# LTC.net
KiCad netlist of a schematic drawn in Altium Designer
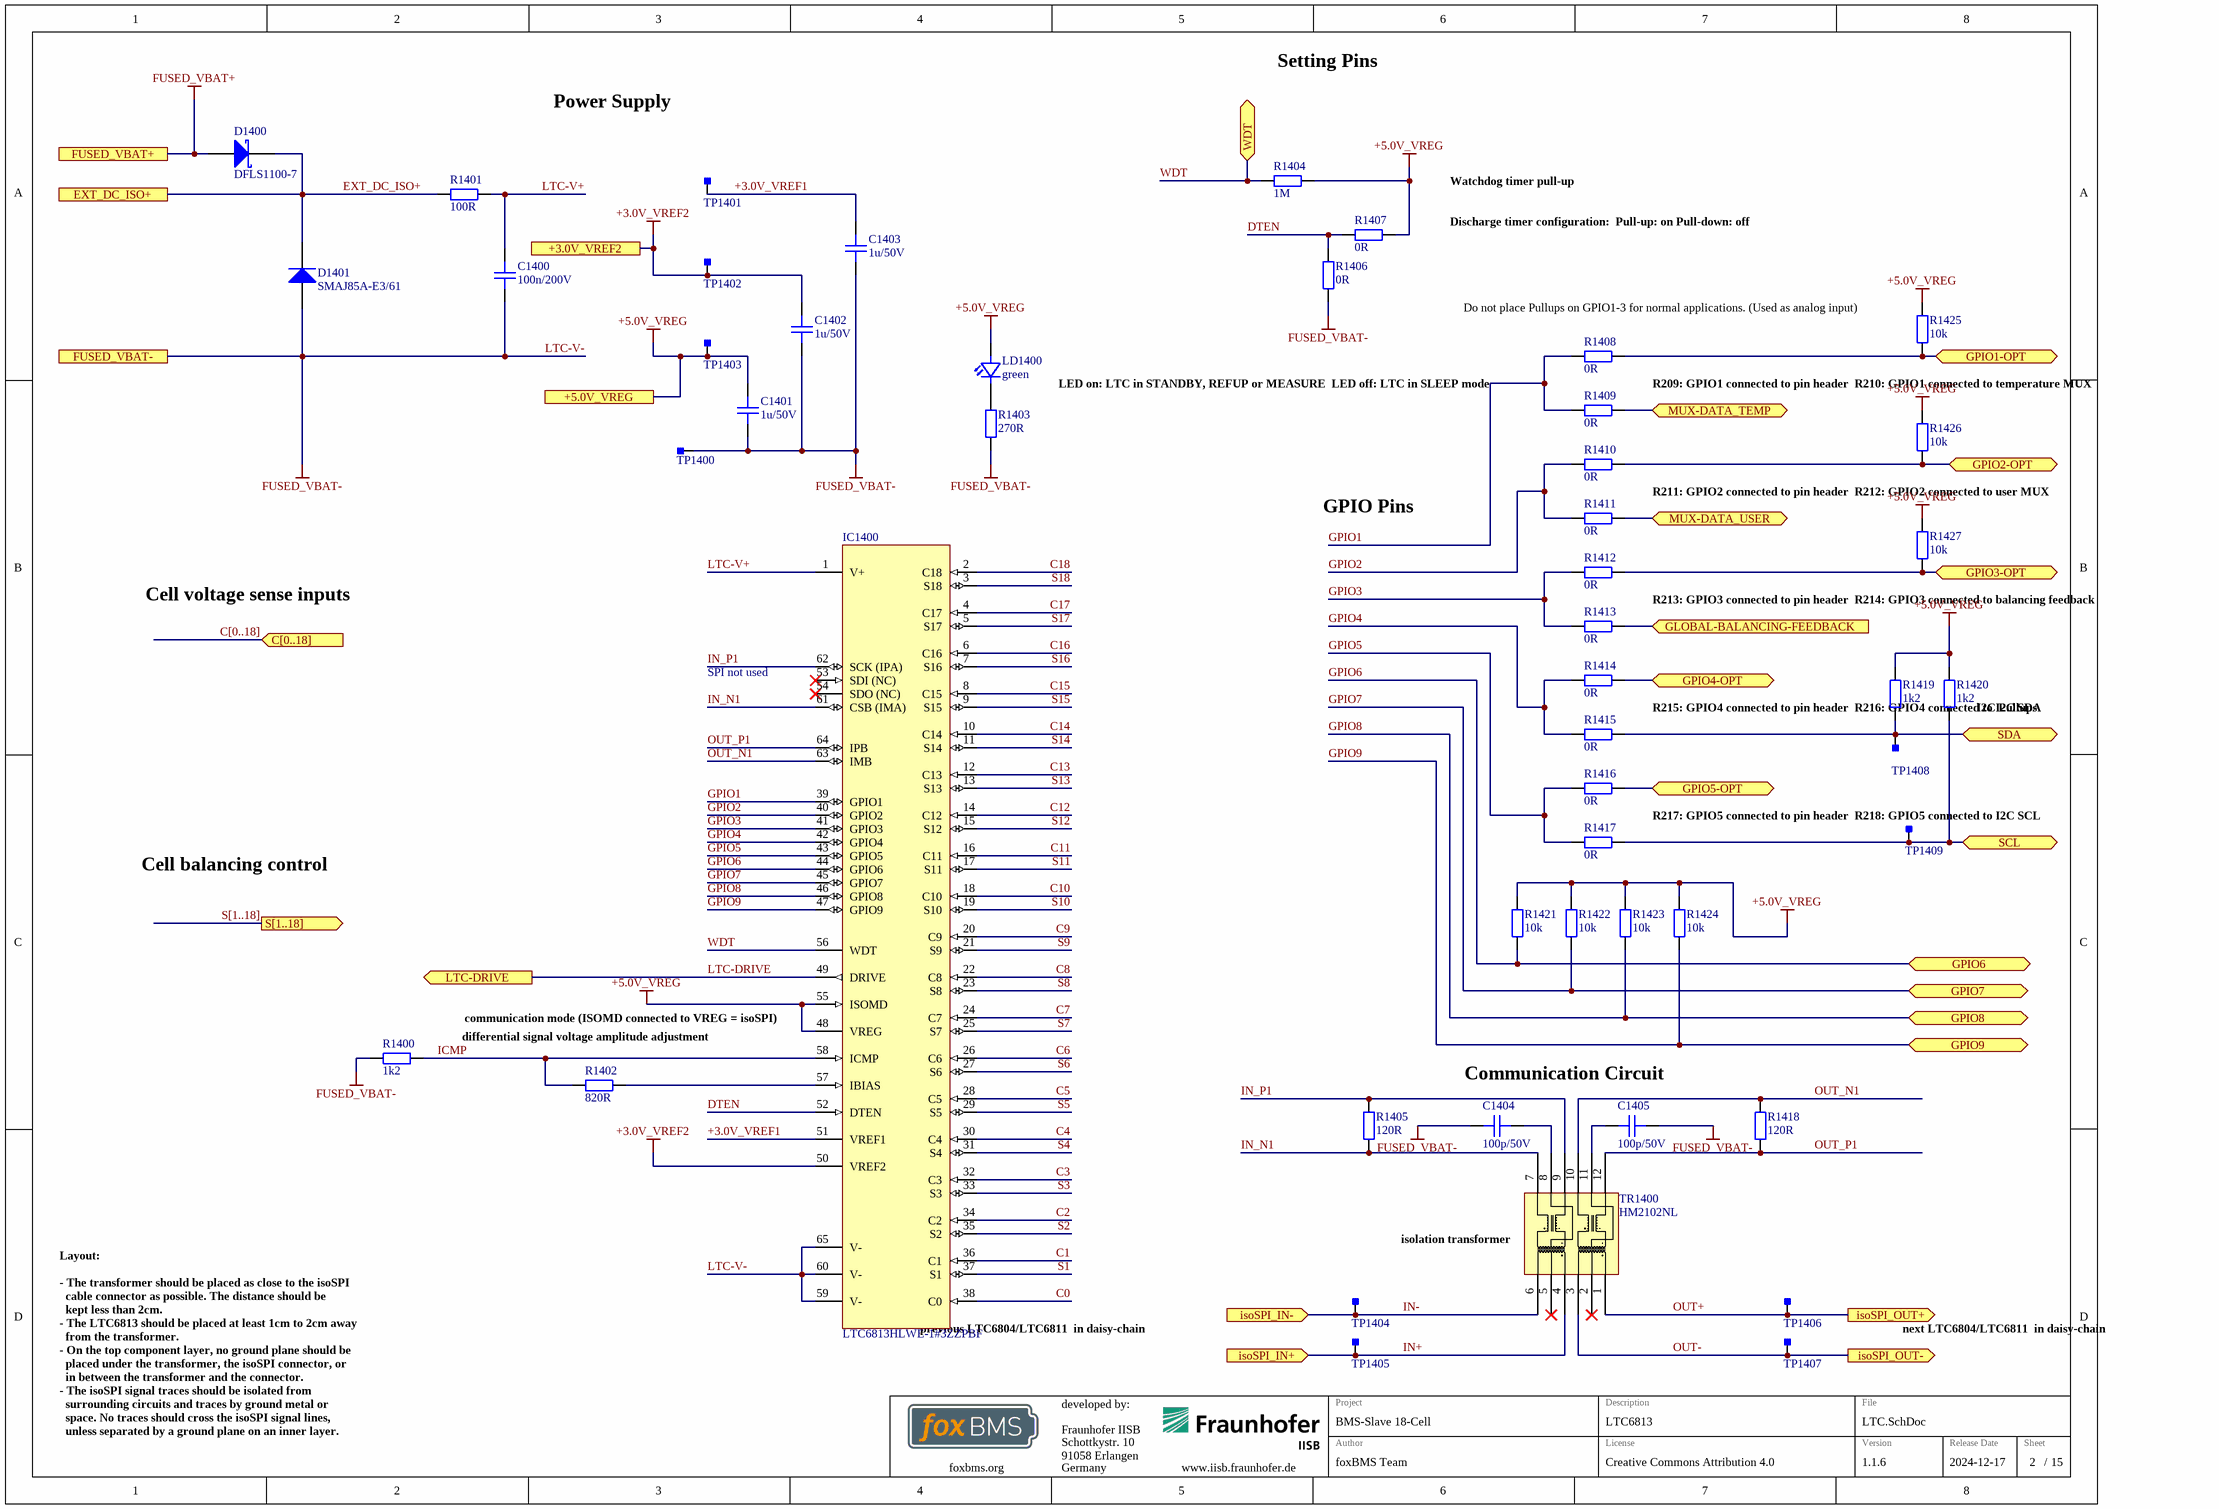
[diagram p0: LTC.SchDoc]

(export (version "E")
  (design (tool "Eeschema 10.0.6"))
  (components
    (comp (ref "C1400")
      (value "100n/200V")
      (footprint "CAPC3216X18N")
      (description "MLCC")
      (fields (field (name "PART NUMBER") "gen_C_ceramic_100n_200V_X7R_1206"))
      (libsource (lib "OE750") (part "C"))
    )
    (comp (ref "C1401")
      (value "1u/50V")
      (footprint "CAPC2012X14N")
      (description "MLCC")
      (fields (field (name "PART NUMBER") "gen_C_ceramic_1u_50V_X7R_0805") (field (name "TOLERANCE") "± 10%"))
      (libsource (lib "OE750") (part "C"))
    )
    (comp (ref "C1402")
      (value "1u/50V")
      (footprint "CAPC2012X14N")
      (description "MLCC")
      (fields (field (name "PART NUMBER") "gen_C_ceramic_1u_50V_X7R_0805") (field (name "TOLERANCE") "± 10%"))
      (libsource (lib "OE750") (part "C"))
    )
    (comp (ref "C1403")
      (value "1u/50V")
      (footprint "CAPC2012X14N")
      (description "MLCC")
      (fields (field (name "PART NUMBER") "gen_C_ceramic_1u_50V_X7R_0805") (field (name "TOLERANCE") "± 10%"))
      (libsource (lib "OE750") (part "C"))
    )
    (comp (ref "C1404")
      (value "100p/50V")
      (footprint "CAPC1608X08N")
      (description "MLCC")
      (fields
        (field (name "PART NUMBER") "gen_C_ceramic_100p_50V_C0G_0603")
        (field (name "TOLERANCE") "± 10%")
      )
      (libsource (lib "OE750") (part "C"))
    )
    (comp (ref "C1405")
      (value "100p/50V")
      (footprint "CAPC1608X08N")
      (description "MLCC")
      (fields
        (field (name "PART NUMBER") "gen_C_ceramic_100p_50V_C0G_0603")
        (field (name "TOLERANCE") "± 10%")
      )
      (libsource (lib "OE750") (part "C"))
    )
    (comp (ref "D1400")
      (value "DFLS1100-7")
      (footprint "DIOD-POWERDI123-2_V")
      (fields (field (name "MANUFACTURER") "Diodes Inc"))
      (libsource (lib "Altium Content Vault") (part "DSKY-AK-2"))
    )
    (comp (ref "D1401")
      (value "SMAJ85A-E3/61")
      (footprint "VISH-DO-214AC-2_L")
      (fields (field (name "MANUFACTURER") "Vishay Semiconductor"))
      (libsource (lib "Altium Content Vault") (part "VISH-K1A2-2"))
    )
    (comp (ref "IC1400")
      (value "LTC6813HLWE-1#3ZZPBF")
      (footprint "TSQFP50P1200X1200X160_HS-65N")
      (description "18 Cell Multicell Battery Monitor, -40 to 125 degC, Pb-Free")
      (fields (field (name "PARTNUMBER") "LTC6811HG-1#PBF") (field (name "MANUFACTURER") "Linear Technology"))
      (libsource (lib "OE750") (part "LTC6813HLWE-1#3ZZPBF"))
    )
    (comp (ref "LD1400")
      (value "green")
      (footprint "LEDC1608X07N")
      (description "TLMG1100-GS08")
      (fields (field (name "PART NUMBER") "LED_0603_green_AECQ") (field (name "MANUFACTURER") "Vishay"))
      (libsource (lib "OE750") (part "D_LED"))
    )
    (comp (ref "R1400")
      (value "1k2")
      (footprint "RESC1608X05N")
      (description "SMD Resistor 1k2 0603")
      (fields (field (name "PART NUMBER") "gen_R_1k2_0603") (field (name "TOLERANCE") "1%"))
      (libsource (lib "OE750") (part "R"))
    )
    (comp (ref "R1401")
      (value "100R")
      (footprint "RESC2012X05N")
      (description "SMD Resistor 100R 0805")
      (fields (field (name "PART NUMBER") "gen_R_100R_0805") (field (name "TOLERANCE") "1%"))
      (libsource (lib "OE750") (part "R"))
    )
    (comp (ref "R1402")
      (value "820R")
      (footprint "RESC1608X05N")
      (description "SMD Resistor 820R 0603")
      (fields (field (name "PART NUMBER") "gen_R_820R_0603") (field (name "TOLERANCE") "1%"))
      (libsource (lib "OE750") (part "R"))
    )
    (comp (ref "R1403")
      (value "270R")
      (footprint "RESC1608X05N")
      (description "SMD Resistor 270R 0603")
      (fields (field (name "PART NUMBER") "gen_R_270R_0603") (field (name "TOLERANCE") "1%"))
      (libsource (lib "OE750") (part "R"))
    )
    (comp (ref "R1404")
      (value "1M")
      (footprint "RESC1608X05N")
      (description "SMD Resistor 1M 0603")
      (fields (field (name "PART NUMBER") "gen_R_1M_0603") (field (name "TOLERANCE") "1%"))
      (libsource (lib "OE750") (part "R"))
    )
    (comp (ref "R1405")
      (value "120R")
      (footprint "RESC1608X05N")
      (description "SMD Resistor 120R 0603")
      (fields (field (name "PART NUMBER") "gen_R_120R_0603") (field (name "TOLERANCE") "1%"))
      (libsource (lib "OE750") (part "R"))
    )
    (comp (ref "R1406")
      (value "0R")
      (footprint "RESC1608X05N")
      (description "SMD Resistor 0R 0603")
      (fields (field (name "PART NUMBER") "gen_R_0R_0603") (field (name "POWER") "0.1W"))
      (libsource (lib "OE750") (part "R"))
    )
    (comp (ref "R1407")
      (value "0R")
      (footprint "RESC1608X05N")
      (description "SMD Resistor 0R 0603")
      (fields (field (name "PART NUMBER") "gen_R_0R_0603") (field (name "POWER") "0.1W"))
      (libsource (lib "OE750") (part "R"))
    )
    (comp (ref "R1408")
      (value "0R")
      (footprint "RESC1608X05N")
      (description "SMD Resistor 0R 0603")
      (fields (field (name "PART NUMBER") "gen_R_0R_0603") (field (name "POWER") "0.1W"))
      (libsource (lib "OE750") (part "R"))
    )
    (comp (ref "R1409")
      (value "0R")
      (footprint "RESC1608X05N")
      (description "SMD Resistor 0R 0603")
      (fields (field (name "PART NUMBER") "gen_R_0R_0603") (field (name "POWER") "0.1W"))
      (libsource (lib "OE750") (part "R"))
    )
    (comp (ref "R1410")
      (value "0R")
      (footprint "RESC1608X05N")
      (description "SMD Resistor 0R 0603")
      (fields (field (name "PART NUMBER") "gen_R_0R_0603") (field (name "POWER") "0.1W"))
      (libsource (lib "OE750") (part "R"))
    )
    (comp (ref "R1411")
      (value "0R")
      (footprint "RESC1608X05N")
      (description "SMD Resistor 0R 0603")
      (fields (field (name "PART NUMBER") "gen_R_0R_0603") (field (name "POWER") "0.1W"))
      (libsource (lib "OE750") (part "R"))
    )
    (comp (ref "R1412")
      (value "0R")
      (footprint "RESC1608X05N")
      (description "SMD Resistor 0R 0603")
      (fields (field (name "PART NUMBER") "gen_R_0R_0603") (field (name "POWER") "0.1W"))
      (libsource (lib "OE750") (part "R"))
    )
    (comp (ref "R1413")
      (value "0R")
      (footprint "RESC1608X05N")
      (description "SMD Resistor 0R 0603")
      (fields (field (name "PART NUMBER") "gen_R_0R_0603") (field (name "POWER") "0.1W"))
      (libsource (lib "OE750") (part "R"))
    )
    (comp (ref "R1414")
      (value "0R")
      (footprint "RESC1608X05N")
      (description "SMD Resistor 0R 0603")
      (fields (field (name "PART NUMBER") "gen_R_0R_0603") (field (name "POWER") "0.1W"))
      (libsource (lib "OE750") (part "R"))
    )
    (comp (ref "R1415")
      (value "0R")
      (footprint "RESC1608X05N")
      (description "SMD Resistor 0R 0603")
      (fields (field (name "PART NUMBER") "gen_R_0R_0603") (field (name "POWER") "0.1W"))
      (libsource (lib "OE750") (part "R"))
    )
    (comp (ref "R1416")
      (value "0R")
      (footprint "RESC1608X05N")
      (description "SMD Resistor 0R 0603")
      (fields (field (name "PART NUMBER") "gen_R_0R_0603") (field (name "POWER") "0.1W"))
      (libsource (lib "OE750") (part "R"))
    )
    (comp (ref "R1417")
      (value "0R")
      (footprint "RESC1608X05N")
      (description "SMD Resistor 0R 0603")
      (fields (field (name "PART NUMBER") "gen_R_0R_0603") (field (name "POWER") "0.1W"))
      (libsource (lib "OE750") (part "R"))
    )
    (comp (ref "R1418")
      (value "120R")
      (footprint "RESC1608X05N")
      (description "SMD Resistor 120R 0603")
      (fields (field (name "PART NUMBER") "gen_R_120R_0603") (field (name "TOLERANCE") "1%"))
      (libsource (lib "OE750") (part "R"))
    )
    (comp (ref "R1419")
      (value "1k2")
      (footprint "RESC1608X05N")
      (description "SMD Resistor 1k2 0603")
      (fields (field (name "PART NUMBER") "gen_R_1k2_0603") (field (name "TOLERANCE") "1%"))
      (libsource (lib "OE750") (part "R"))
    )
    (comp (ref "R1420")
      (value "1k2")
      (footprint "RESC1608X05N")
      (description "SMD Resistor 1k2 0603")
      (fields (field (name "PART NUMBER") "gen_R_1k2_0603") (field (name "TOLERANCE") "1%"))
      (libsource (lib "OE750") (part "R"))
    )
    (comp (ref "R1421")
      (value "10k")
      (footprint "RESC1608X05N")
      (description "SMD Resistor 10k 0603")
      (fields (field (name "PART NUMBER") "gen_R_10k_0603") (field (name "TOLERANCE") "1%"))
      (libsource (lib "OE750") (part "R"))
    )
    (comp (ref "R1422")
      (value "10k")
      (footprint "RESC1608X05N")
      (description "SMD Resistor 10k 0603")
      (fields (field (name "PART NUMBER") "gen_R_10k_0603") (field (name "TOLERANCE") "1%"))
      (libsource (lib "OE750") (part "R"))
    )
    (comp (ref "R1423")
      (value "10k")
      (footprint "RESC1608X05N")
      (description "SMD Resistor 10k 0603")
      (fields (field (name "PART NUMBER") "gen_R_10k_0603") (field (name "TOLERANCE") "1%"))
      (libsource (lib "OE750") (part "R"))
    )
    (comp (ref "R1424")
      (value "10k")
      (footprint "RESC1608X05N")
      (description "SMD Resistor 10k 0603")
      (fields (field (name "PART NUMBER") "gen_R_10k_0603") (field (name "TOLERANCE") "1%"))
      (libsource (lib "OE750") (part "R"))
    )
    (comp (ref "R1425")
      (value "10k")
      (footprint "RESC1608X05N")
      (description "SMD Resistor 10k 0603")
      (fields (field (name "PART NUMBER") "gen_R_10k_0603") (field (name "TOLERANCE") "1%"))
      (libsource (lib "OE750") (part "R"))
    )
    (comp (ref "R1426")
      (value "10k")
      (footprint "RESC1608X05N")
      (description "SMD Resistor 10k 0603")
      (fields (field (name "PART NUMBER") "gen_R_10k_0603") (field (name "TOLERANCE") "1%"))
      (libsource (lib "OE750") (part "R"))
    )
    (comp (ref "R1427")
      (value "10k")
      (footprint "RESC1608X05N")
      (description "SMD Resistor 10k 0603")
      (fields (field (name "PART NUMBER") "gen_R_10k_0603") (field (name "TOLERANCE") "1%"))
      (libsource (lib "OE750") (part "R"))
    )
    (comp (ref "TP1400")
      (value "Testpoint_Square")
      (footprint "Testpoint_S1")
      (description "Testpoint, square")
      (libsource (lib "OE750") (part "Testpoint_Square"))
    )
    (comp (ref "TP1401")
      (value "Testpoint_Square")
      (footprint "Testpoint_S1")
      (description "Testpoint, square")
      (libsource (lib "OE750") (part "Testpoint_Square"))
    )
    (comp (ref "TP1402")
      (value "Testpoint_Square")
      (footprint "Testpoint_S1")
      (description "Testpoint, square")
      (libsource (lib "OE750") (part "Testpoint_Square"))
    )
    (comp (ref "TP1403")
      (value "Testpoint_Square")
      (footprint "Testpoint_S1")
      (description "Testpoint, square")
      (libsource (lib "OE750") (part "Testpoint_Square"))
    )
    (comp (ref "TP1404")
      (value "Testpoint_Square")
      (footprint "Testpoint_S1")
      (description "Testpoint, square")
      (libsource (lib "OE750") (part "Testpoint_Square"))
    )
    (comp (ref "TP1405")
      (value "Testpoint_Square")
      (footprint "Testpoint_S1")
      (description "Testpoint, square")
      (libsource (lib "OE750") (part "Testpoint_Square"))
    )
    (comp (ref "TP1406")
      (value "Testpoint_Square")
      (footprint "Testpoint_S1")
      (description "Testpoint, square")
      (libsource (lib "OE750") (part "Testpoint_Square"))
    )
    (comp (ref "TP1407")
      (value "Testpoint_Square")
      (footprint "Testpoint_S1")
      (description "Testpoint, square")
      (libsource (lib "OE750") (part "Testpoint_Square"))
    )
    (comp (ref "TP1408")
      (value "Testpoint_Square")
      (footprint "Testpoint_S1")
      (description "Testpoint, square")
      (libsource (lib "OE750") (part "Testpoint_Square"))
    )
    (comp (ref "TP1409")
      (value "Testpoint_Square")
      (footprint "Testpoint_S1")
      (description "Testpoint, square")
      (libsource (lib "OE750") (part "Testpoint_Square"))
    )
    (comp (ref "TR1400")
      (value "HM2102NL")
      (footprint "HM2102NL")
      (description "Pulse HM2102NL BMS Transformer")
      (fields (field (name "MANUFACTURER") "Pulse"))
      (libsource (lib "OE750") (part "HM2102NL"))
    )
  )
  (nets
    (net (code "1") (name "+3.0V_VREF2") (class "Default")
      (node (ref "C1402") (pin "2") (pinfunction "2_2") (pintype "passive"))
      (node (ref "IC1400") (pin "50") (pinfunction "VREF2_50") (pintype "passive"))
      (node (ref "TP1402") (pin "1") (pinfunction "1_1") (pintype "passive"))
    )
    (net (code "2") (name "+5.0V_VREG") (class "Default")
      (node (ref "C1401") (pin "2") (pinfunction "2_2") (pintype "passive"))
      (node (ref "IC1400") (pin "48") (pinfunction "VREG_48") (pintype "power_in"))
      (node (ref "IC1400") (pin "55") (pinfunction "ISOMD_55") (pintype "input"))
      (node (ref "LD1400") (pin "2") (pinfunction "A_2") (pintype "passive"))
      (node (ref "R1404") (pin "2") (pinfunction "2_2") (pintype "passive"))
      (node (ref "R1407") (pin "2") (pinfunction "2_2") (pintype "passive"))
      (node (ref "R1419") (pin "2") (pinfunction "2_2") (pintype "passive"))
      (node (ref "R1420") (pin "2") (pinfunction "2_2") (pintype "passive"))
      (node (ref "R1421") (pin "2") (pinfunction "2_2") (pintype "passive"))
      (node (ref "R1422") (pin "2") (pinfunction "2_2") (pintype "passive"))
      (node (ref "R1423") (pin "2") (pinfunction "2_2") (pintype "passive"))
      (node (ref "R1424") (pin "2") (pinfunction "2_2") (pintype "passive"))
      (node (ref "R1425") (pin "2") (pinfunction "2_2") (pintype "passive"))
      (node (ref "R1426") (pin "2") (pinfunction "2_2") (pintype "passive"))
      (node (ref "R1427") (pin "2") (pinfunction "2_2") (pintype "passive"))
      (node (ref "TP1403") (pin "1") (pinfunction "1_1") (pintype "passive"))
    )
    (net (code "3") (name "/+3.0V_VREF1") (class "Default")
      (node (ref "C1403") (pin "2") (pinfunction "2_2") (pintype "passive"))
      (node (ref "IC1400") (pin "51") (pinfunction "VREF1_51") (pintype "passive"))
      (node (ref "TP1401") (pin "1") (pinfunction "1_1") (pintype "passive"))
    )
    (net (code "4") (name "/C0") (class "Default")
      (node (ref "IC1400") (pin "38") (pinfunction "C0_38") (pintype "input"))
    )
    (net (code "5") (name "/C1") (class "Default")
      (node (ref "IC1400") (pin "36") (pinfunction "C1_36") (pintype "input"))
    )
    (net (code "6") (name "/C2") (class "Default")
      (node (ref "IC1400") (pin "34") (pinfunction "C2_34") (pintype "input"))
    )
    (net (code "7") (name "/C3") (class "Default")
      (node (ref "IC1400") (pin "32") (pinfunction "C3_32") (pintype "input"))
    )
    (net (code "8") (name "/C4") (class "Default")
      (node (ref "IC1400") (pin "30") (pinfunction "C4_30") (pintype "input"))
    )
    (net (code "9") (name "/C5") (class "Default")
      (node (ref "IC1400") (pin "28") (pinfunction "C5_28") (pintype "input"))
    )
    (net (code "10") (name "/C6") (class "Default")
      (node (ref "IC1400") (pin "26") (pinfunction "C6_26") (pintype "input"))
    )
    (net (code "11") (name "/C7") (class "Default")
      (node (ref "IC1400") (pin "24") (pinfunction "C7_24") (pintype "input"))
    )
    (net (code "12") (name "/C8") (class "Default")
      (node (ref "IC1400") (pin "22") (pinfunction "C8_22") (pintype "input"))
    )
    (net (code "13") (name "/C9") (class "Default")
      (node (ref "IC1400") (pin "20") (pinfunction "C9_20") (pintype "input"))
    )
    (net (code "14") (name "/C10") (class "Default")
      (node (ref "IC1400") (pin "18") (pinfunction "C10_18") (pintype "input"))
    )
    (net (code "15") (name "/C11") (class "Default")
      (node (ref "IC1400") (pin "16") (pinfunction "C11_16") (pintype "input"))
    )
    (net (code "16") (name "/C12") (class "Default")
      (node (ref "IC1400") (pin "14") (pinfunction "C12_14") (pintype "input"))
    )
    (net (code "17") (name "/C13") (class "Default")
      (node (ref "IC1400") (pin "12") (pinfunction "C13_12") (pintype "input"))
    )
    (net (code "18") (name "/C14") (class "Default")
      (node (ref "IC1400") (pin "10") (pinfunction "C14_10") (pintype "input"))
    )
    (net (code "19") (name "/C15") (class "Default")
      (node (ref "IC1400") (pin "8") (pinfunction "C15_8") (pintype "input"))
    )
    (net (code "20") (name "/C16") (class "Default")
      (node (ref "IC1400") (pin "6") (pinfunction "C16_6") (pintype "input"))
    )
    (net (code "21") (name "/C17") (class "Default")
      (node (ref "IC1400") (pin "4") (pinfunction "C17_4") (pintype "input"))
    )
    (net (code "22") (name "/C18") (class "Default")
      (node (ref "IC1400") (pin "2") (pinfunction "C18_2") (pintype "input"))
    )
    (net (code "24") (name "/DTEN") (class "Default")
      (node (ref "IC1400") (pin "52") (pinfunction "DTEN_52") (pintype "input"))
      (node (ref "R1406") (pin "2") (pinfunction "2_2") (pintype "passive"))
      (node (ref "R1407") (pin "1") (pinfunction "1_1") (pintype "passive"))
    )
    (net (code "25") (name "/EXT_DC_ISO+") (class "Default")
      (node (ref "D1400") (pin "2") (pinfunction "K_2") (pintype "passive"))
      (node (ref "D1401") (pin "1") (pinfunction "K_1") (pintype "passive"))
      (node (ref "R1401") (pin "1") (pinfunction "1_1") (pintype "passive"))
    )
    (net (code "26") (name "/GLOBAL-BALANCING-FEEDBACK") (class "Default")
      (node (ref "R1413") (pin "1") (pinfunction "1_1") (pintype "passive"))
    )
    (net (code "27") (name "/GPIO1") (class "Default")
      (node (ref "IC1400") (pin "39") (pinfunction "GPIO1_39") (pintype "bidirectional"))
      (node (ref "R1408") (pin "2") (pinfunction "2_2") (pintype "passive"))
      (node (ref "R1409") (pin "2") (pinfunction "2_2") (pintype "passive"))
    )
    (net (code "28") (name "/GPIO1-OPT") (class "Default")
      (node (ref "R1408") (pin "1") (pinfunction "1_1") (pintype "passive"))
      (node (ref "R1425") (pin "1") (pinfunction "1_1") (pintype "passive"))
    )
    (net (code "29") (name "/GPIO2") (class "Default")
      (node (ref "IC1400") (pin "40") (pinfunction "GPIO2_40") (pintype "bidirectional"))
      (node (ref "R1410") (pin "2") (pinfunction "2_2") (pintype "passive"))
      (node (ref "R1411") (pin "2") (pinfunction "2_2") (pintype "passive"))
    )
    (net (code "30") (name "/GPIO2-OPT") (class "Default")
      (node (ref "R1410") (pin "1") (pinfunction "1_1") (pintype "passive"))
      (node (ref "R1426") (pin "1") (pinfunction "1_1") (pintype "passive"))
    )
    (net (code "31") (name "/GPIO3") (class "Default")
      (node (ref "IC1400") (pin "41") (pinfunction "GPIO3_41") (pintype "bidirectional"))
      (node (ref "R1412") (pin "2") (pinfunction "2_2") (pintype "passive"))
      (node (ref "R1413") (pin "2") (pinfunction "2_2") (pintype "passive"))
    )
    (net (code "32") (name "/GPIO3-OPT") (class "Default")
      (node (ref "R1412") (pin "1") (pinfunction "1_1") (pintype "passive"))
      (node (ref "R1427") (pin "1") (pinfunction "1_1") (pintype "passive"))
    )
    (net (code "33") (name "/GPIO4") (class "Default")
      (node (ref "IC1400") (pin "42") (pinfunction "GPIO4_42") (pintype "bidirectional"))
      (node (ref "R1414") (pin "2") (pinfunction "2_2") (pintype "passive"))
      (node (ref "R1415") (pin "2") (pinfunction "2_2") (pintype "passive"))
    )
    (net (code "34") (name "/GPIO4-OPT") (class "Default")
      (node (ref "R1414") (pin "1") (pinfunction "1_1") (pintype "passive"))
    )
    (net (code "35") (name "/GPIO5") (class "Default")
      (node (ref "IC1400") (pin "43") (pinfunction "GPIO5_43") (pintype "bidirectional"))
      (node (ref "R1416") (pin "2") (pinfunction "2_2") (pintype "passive"))
      (node (ref "R1417") (pin "2") (pinfunction "2_2") (pintype "passive"))
    )
    (net (code "36") (name "/GPIO5-OPT") (class "Default")
      (node (ref "R1416") (pin "1") (pinfunction "1_1") (pintype "passive"))
    )
    (net (code "37") (name "/GPIO6") (class "Default")
      (node (ref "IC1400") (pin "44") (pinfunction "GPIO6_44") (pintype "bidirectional"))
      (node (ref "R1421") (pin "1") (pinfunction "1_1") (pintype "passive"))
    )
    (net (code "38") (name "/GPIO7") (class "Default")
      (node (ref "IC1400") (pin "45") (pinfunction "GPIO7_45") (pintype "bidirectional"))
      (node (ref "R1422") (pin "1") (pinfunction "1_1") (pintype "passive"))
    )
    (net (code "39") (name "/GPIO8") (class "Default")
      (node (ref "IC1400") (pin "46") (pinfunction "GPIO8_46") (pintype "bidirectional"))
      (node (ref "R1423") (pin "1") (pinfunction "1_1") (pintype "passive"))
    )
    (net (code "40") (name "/GPIO9") (class "Default")
      (node (ref "IC1400") (pin "47") (pinfunction "GPIO9_47") (pintype "bidirectional"))
      (node (ref "R1424") (pin "1") (pinfunction "1_1") (pintype "passive"))
    )
    (net (code "41") (name "/ICMP") (class "Default")
      (node (ref "IC1400") (pin "58") (pinfunction "ICMP_58") (pintype "input"))
      (node (ref "R1400") (pin "2") (pinfunction "2_2") (pintype "passive"))
      (node (ref "R1402") (pin "1") (pinfunction "1_1") (pintype "passive"))
    )
    (net (code "42") (name "/IN+") (class "Default")
      (node (ref "TP1405") (pin "1") (pinfunction "1_1") (pintype "passive"))
      (node (ref "TR1400") (pin "4") (pintype "passive"))
    )
    (net (code "43") (name "/IN-") (class "Default")
      (node (ref "TP1404") (pin "1") (pinfunction "1_1") (pintype "passive"))
      (node (ref "TR1400") (pin "6") (pintype "passive"))
    )
    (net (code "44") (name "/IN_N1") (class "Default")
      (node (ref "IC1400") (pin "61") (pinfunction "CSB_(IMA)_61") (pintype "bidirectional"))
      (node (ref "R1405") (pin "2") (pinfunction "2_2") (pintype "passive"))
      (node (ref "TR1400") (pin "7") (pintype "passive"))
    )
    (net (code "45") (name "/IN_P1") (class "Default")
      (node (ref "IC1400") (pin "62") (pinfunction "SCK_(IPA)_62") (pintype "bidirectional"))
      (node (ref "R1405") (pin "1") (pinfunction "1_1") (pintype "passive"))
      (node (ref "TR1400") (pin "9") (pintype "passive"))
    )
    (net (code "46") (name "/LTC-DRIVE") (class "Default")
      (node (ref "IC1400") (pin "49") (pinfunction "DRIVE_49") (pintype "output"))
    )
    (net (code "47") (name "/LTC-V+") (class "Default")
      (node (ref "C1400") (pin "1") (pinfunction "1_1") (pintype "passive"))
      (node (ref "IC1400") (pin "1") (pinfunction "V+_1") (pintype "power_in"))
      (node (ref "R1401") (pin "2") (pinfunction "2_2") (pintype "passive"))
    )
    (net (code "48") (name "/MUX-DATA_TEMP") (class "Default")
      (node (ref "R1409") (pin "1") (pinfunction "1_1") (pintype "passive"))
    )
    (net (code "49") (name "/MUX-DATA_USER") (class "Default")
      (node (ref "R1411") (pin "1") (pinfunction "1_1") (pintype "passive"))
    )
    (net (code "50") (name "/OUT+") (class "Default")
      (node (ref "TP1406") (pin "1") (pinfunction "1_1") (pintype "passive"))
      (node (ref "TR1400") (pin "1") (pintype "passive"))
    )
    (net (code "51") (name "/OUT-") (class "Default")
      (node (ref "TP1407") (pin "1") (pinfunction "1_1") (pintype "passive"))
      (node (ref "TR1400") (pin "3") (pintype "passive"))
    )
    (net (code "52") (name "/OUT_N1") (class "Default")
      (node (ref "IC1400") (pin "63") (pinfunction "IMB_63") (pintype "bidirectional"))
      (node (ref "R1418") (pin "2") (pinfunction "2_2") (pintype "passive"))
      (node (ref "TR1400") (pin "10") (pintype "passive"))
    )
    (net (code "53") (name "/OUT_P1") (class "Default")
      (node (ref "IC1400") (pin "64") (pinfunction "IPB_64") (pintype "bidirectional"))
      (node (ref "R1418") (pin "1") (pinfunction "1_1") (pintype "passive"))
      (node (ref "TR1400") (pin "12") (pintype "passive"))
    )
    (net (code "54") (name "/S1") (class "Default")
      (node (ref "IC1400") (pin "37") (pinfunction "S1_37") (pintype "bidirectional"))
    )
    (net (code "55") (name "/S2") (class "Default")
      (node (ref "IC1400") (pin "35") (pinfunction "S2_35") (pintype "bidirectional"))
    )
    (net (code "56") (name "/S3") (class "Default")
      (node (ref "IC1400") (pin "33") (pinfunction "S3_33") (pintype "bidirectional"))
    )
    (net (code "57") (name "/S4") (class "Default")
      (node (ref "IC1400") (pin "31") (pinfunction "S4_31") (pintype "bidirectional"))
    )
    (net (code "58") (name "/S5") (class "Default")
      (node (ref "IC1400") (pin "29") (pinfunction "S5_29") (pintype "bidirectional"))
    )
    (net (code "59") (name "/S6") (class "Default")
      (node (ref "IC1400") (pin "27") (pinfunction "S6_27") (pintype "bidirectional"))
    )
    (net (code "60") (name "/S7") (class "Default")
      (node (ref "IC1400") (pin "25") (pinfunction "S7_25") (pintype "bidirectional"))
    )
    (net (code "61") (name "/S8") (class "Default")
      (node (ref "IC1400") (pin "23") (pinfunction "S8_23") (pintype "bidirectional"))
    )
    (net (code "62") (name "/S9") (class "Default")
      (node (ref "IC1400") (pin "21") (pinfunction "S9_21") (pintype "bidirectional"))
    )
    (net (code "63") (name "/S10") (class "Default")
      (node (ref "IC1400") (pin "19") (pinfunction "S10_19") (pintype "bidirectional"))
    )
    (net (code "64") (name "/S11") (class "Default")
      (node (ref "IC1400") (pin "17") (pinfunction "S11_17") (pintype "bidirectional"))
    )
    (net (code "65") (name "/S12") (class "Default")
      (node (ref "IC1400") (pin "15") (pinfunction "S12_15") (pintype "bidirectional"))
    )
    (net (code "66") (name "/S13") (class "Default")
      (node (ref "IC1400") (pin "13") (pinfunction "S13_13") (pintype "bidirectional"))
    )
    (net (code "67") (name "/S14") (class "Default")
      (node (ref "IC1400") (pin "11") (pinfunction "S14_11") (pintype "bidirectional"))
    )
    (net (code "68") (name "/S15") (class "Default")
      (node (ref "IC1400") (pin "9") (pinfunction "S15_9") (pintype "bidirectional"))
    )
    (net (code "69") (name "/S16") (class "Default")
      (node (ref "IC1400") (pin "7") (pinfunction "S16_7") (pintype "bidirectional"))
    )
    (net (code "70") (name "/S17") (class "Default")
      (node (ref "IC1400") (pin "5") (pinfunction "S17_5") (pintype "bidirectional"))
    )
    (net (code "71") (name "/S18") (class "Default")
      (node (ref "IC1400") (pin "3") (pinfunction "S18_3") (pintype "bidirectional"))
    )
    (net (code "72") (name "/SCL") (class "Default")
      (node (ref "R1417") (pin "1") (pinfunction "1_1") (pintype "passive"))
      (node (ref "R1420") (pin "1") (pinfunction "1_1") (pintype "passive"))
      (node (ref "TP1409") (pin "1") (pinfunction "1_1") (pintype "passive"))
    )
    (net (code "73") (name "/SDA") (class "Default")
      (node (ref "R1415") (pin "1") (pinfunction "1_1") (pintype "passive"))
      (node (ref "R1419") (pin "1") (pinfunction "1_1") (pintype "passive"))
      (node (ref "TP1408") (pin "1") (pinfunction "1_1") (pintype "passive"))
    )
    (net (code "75") (name "/WDT") (class "Default")
      (node (ref "IC1400") (pin "56") (pinfunction "WDT_56") (pintype "tri_state"))
      (node (ref "R1404") (pin "1") (pinfunction "1_1") (pintype "passive"))
    )
    (net (code "76") (name "FUSED_VBAT+") (class "Default")
      (node (ref "D1400") (pin "1") (pinfunction "A_1") (pintype "passive"))
    )
    (net (code "77") (name "FUSED_VBAT-") (class "Default")
      (node (ref "C1400") (pin "2") (pinfunction "2_2") (pintype "passive"))
      (node (ref "C1401") (pin "1") (pinfunction "1_1") (pintype "passive"))
      (node (ref "C1402") (pin "1") (pinfunction "1_1") (pintype "passive"))
      (node (ref "C1403") (pin "1") (pinfunction "1_1") (pintype "passive"))
      (node (ref "C1404") (pin "1") (pinfunction "1_1") (pintype "passive"))
      (node (ref "C1405") (pin "1") (pinfunction "1_1") (pintype "passive"))
      (node (ref "D1401") (pin "2") (pinfunction "A_2") (pintype "passive"))
      (node (ref "IC1400") (pin "59") (pinfunction "V-_59") (pintype "power_in"))
      (node (ref "IC1400") (pin "60") (pinfunction "V-_60") (pintype "power_in"))
      (node (ref "IC1400") (pin "65") (pinfunction "V-_65") (pintype "power_in"))
      (node (ref "R1400") (pin "1") (pinfunction "1_1") (pintype "passive"))
      (node (ref "R1403") (pin "1") (pinfunction "1_1") (pintype "passive"))
      (node (ref "R1406") (pin "1") (pinfunction "1_1") (pintype "passive"))
      (node (ref "TP1400") (pin "1") (pinfunction "1_1") (pintype "passive"))
    )
    (net (code "78") (name "Net-(C1404-Pad2)") (class "Default")
      (node (ref "C1404") (pin "2") (pinfunction "2_2") (pintype "passive"))
      (node (ref "TR1400") (pin "8") (pintype "passive"))
    )
    (net (code "79") (name "Net-(C1405-Pad2)") (class "Default")
      (node (ref "C1405") (pin "2") (pinfunction "2_2") (pintype "passive"))
      (node (ref "TR1400") (pin "11") (pintype "passive"))
    )
    (net (code "80") (name "Net-(IC1400-IBIAS)") (class "Default")
      (node (ref "IC1400") (pin "57") (pinfunction "IBIAS_57") (pintype "input"))
      (node (ref "R1402") (pin "2") (pinfunction "2_2") (pintype "passive"))
    )
    (net (code "81") (name "Net-(LD1400-C)") (class "Default")
      (node (ref "LD1400") (pin "1") (pinfunction "C_1") (pintype "passive"))
      (node (ref "R1403") (pin "2") (pinfunction "2_2") (pintype "passive"))
    )
    (net (code "82") (name "unconnected-(IC1400-SDI_(NC)-Pad53)") (class "Default")
      (node (ref "IC1400") (pin "53") (pinfunction "SDI_(NC)_53") (pintype "input+no_connect"))
    )
    (net (code "83") (name "unconnected-(IC1400-SDO_(NC)-Pad54)") (class "Default")
      (node (ref "IC1400") (pin "54") (pinfunction "SDO_(NC)_54") (pintype "open_collector+no_connect"))
    )
    (net (code "84") (name "unconnected-(TR1400-Pad2)") (class "Default")
      (node (ref "TR1400") (pin "2") (pintype "passive+no_connect"))
    )
    (net (code "85") (name "unconnected-(TR1400-Pad5)") (class "Default")
      (node (ref "TR1400") (pin "5") (pintype "passive+no_connect"))
    )
  )
)
